# fpga-serdes-power.net
KiCad netlist of a schematic drawn in Altium Designer
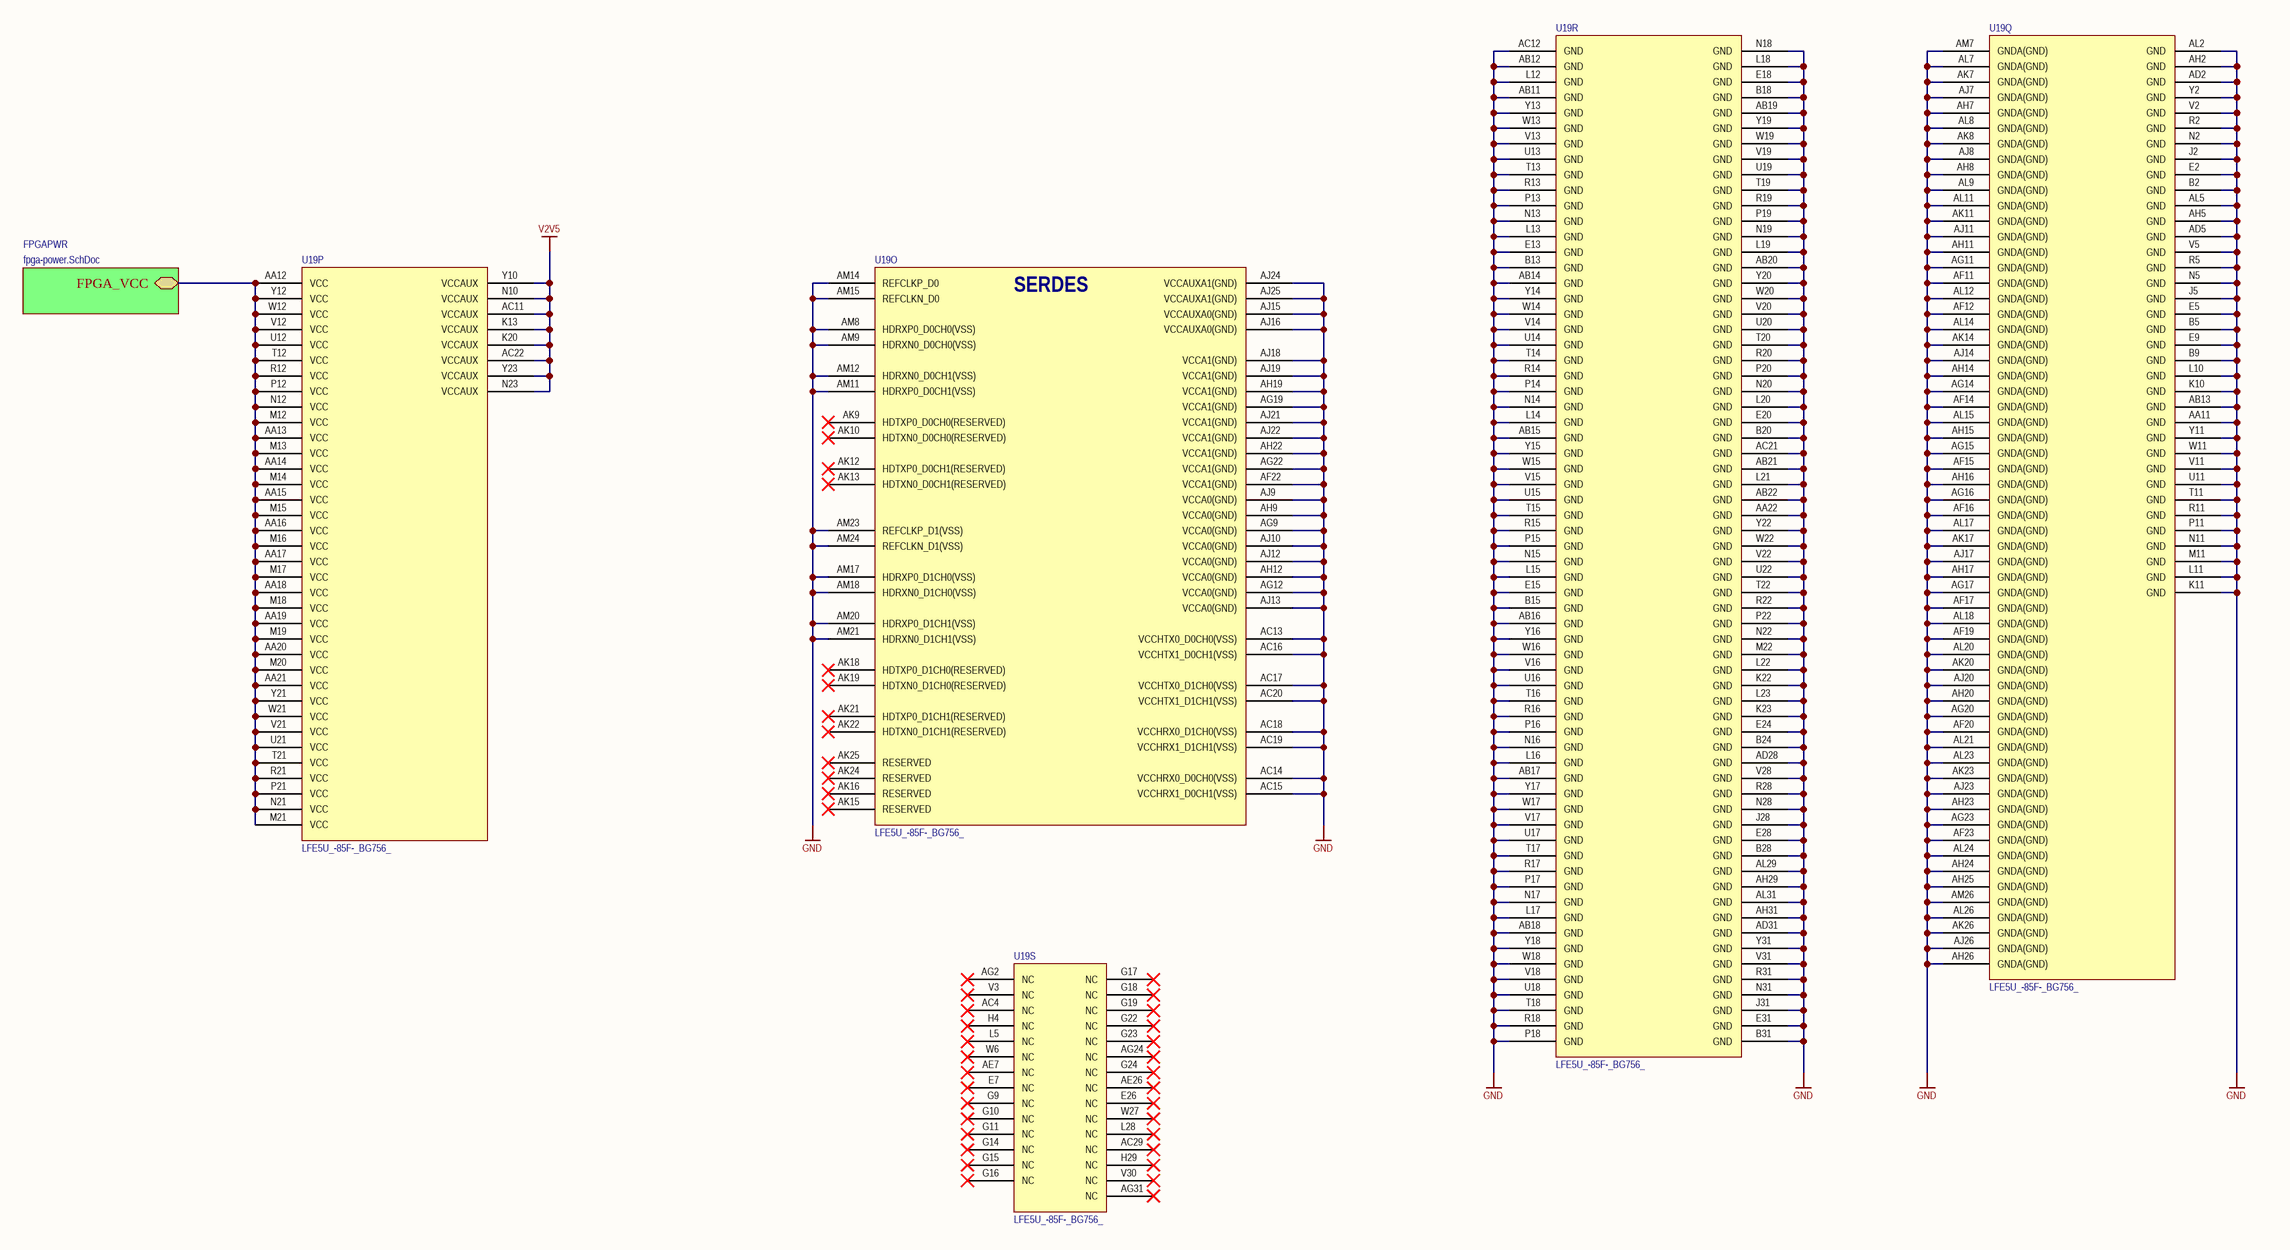
[diagram p0: fpga-serdes-power.SchDoc]

(export (version "E")
  (design (tool "Eeschema 10.0.6"))
  (components
    (comp (ref "U19")
      (value "LFE5U_-85F-_BG756_")
      (footprint "lattice:caBGA756")
      (description "ECP5 FPGA, 85k LUT, 756-caBGA")
      (fields (field (name "MANUFACTURER") "Lattice Semiconductor"))
      (libsource (lib "lattice") (part "LFE5U_-85F-_BG756_"))
    )
  )
  (nets
    (net (code "1") (name "/FPGA_VCC") (class "Default")
      (node (ref "U19") (pin "AA12") (pinfunction "VCC_AA12") (pintype "power_in"))
      (node (ref "U19") (pin "AA13") (pinfunction "VCC_AA13") (pintype "power_in"))
      (node (ref "U19") (pin "AA14") (pinfunction "VCC_AA14") (pintype "power_in"))
      (node (ref "U19") (pin "AA15") (pinfunction "VCC_AA15") (pintype "power_in"))
      (node (ref "U19") (pin "AA16") (pinfunction "VCC_AA16") (pintype "power_in"))
      (node (ref "U19") (pin "AA17") (pinfunction "VCC_AA17") (pintype "power_in"))
      (node (ref "U19") (pin "AA18") (pinfunction "VCC_AA18") (pintype "power_in"))
      (node (ref "U19") (pin "AA19") (pinfunction "VCC_AA19") (pintype "power_in"))
      (node (ref "U19") (pin "AA20") (pinfunction "VCC_AA20") (pintype "power_in"))
      (node (ref "U19") (pin "AA21") (pinfunction "VCC_AA21") (pintype "power_in"))
      (node (ref "U19") (pin "M12") (pinfunction "VCC_M12") (pintype "power_in"))
      (node (ref "U19") (pin "M13") (pinfunction "VCC_M13") (pintype "power_in"))
      (node (ref "U19") (pin "M14") (pinfunction "VCC_M14") (pintype "power_in"))
      (node (ref "U19") (pin "M15") (pinfunction "VCC_M15") (pintype "power_in"))
      (node (ref "U19") (pin "M16") (pinfunction "VCC_M16") (pintype "power_in"))
      (node (ref "U19") (pin "M17") (pinfunction "VCC_M17") (pintype "power_in"))
      (node (ref "U19") (pin "M18") (pinfunction "VCC_M18") (pintype "power_in"))
      (node (ref "U19") (pin "M19") (pinfunction "VCC_M19") (pintype "power_in"))
      (node (ref "U19") (pin "M20") (pinfunction "VCC_M20") (pintype "power_in"))
      (node (ref "U19") (pin "M21") (pinfunction "VCC_M21") (pintype "power_in"))
      (node (ref "U19") (pin "N12") (pinfunction "VCC_N12") (pintype "power_in"))
      (node (ref "U19") (pin "N21") (pinfunction "VCC_N21") (pintype "power_in"))
      (node (ref "U19") (pin "P12") (pinfunction "VCC_P12") (pintype "power_in"))
      (node (ref "U19") (pin "P21") (pinfunction "VCC_P21") (pintype "power_in"))
      (node (ref "U19") (pin "R12") (pinfunction "VCC_R12") (pintype "power_in"))
      (node (ref "U19") (pin "R21") (pinfunction "VCC_R21") (pintype "power_in"))
      (node (ref "U19") (pin "T12") (pinfunction "VCC_T12") (pintype "power_in"))
      (node (ref "U19") (pin "T21") (pinfunction "VCC_T21") (pintype "power_in"))
      (node (ref "U19") (pin "U12") (pinfunction "VCC_U12") (pintype "power_in"))
      (node (ref "U19") (pin "U21") (pinfunction "VCC_U21") (pintype "power_in"))
      (node (ref "U19") (pin "V12") (pinfunction "VCC_V12") (pintype "power_in"))
      (node (ref "U19") (pin "V21") (pinfunction "VCC_V21") (pintype "power_in"))
      (node (ref "U19") (pin "W12") (pinfunction "VCC_W12") (pintype "power_in"))
      (node (ref "U19") (pin "W21") (pinfunction "VCC_W21") (pintype "power_in"))
      (node (ref "U19") (pin "Y12") (pinfunction "VCC_Y12") (pintype "power_in"))
      (node (ref "U19") (pin "Y21") (pinfunction "VCC_Y21") (pintype "power_in"))
    )
    (net (code "2") (name "GND") (class "Default")
      (node (ref "U19") (pin "AA11") (pinfunction "GND_AA11") (pintype "power_in"))
      (node (ref "U19") (pin "AA22") (pinfunction "GND_AA22") (pintype "power_in"))
      (node (ref "U19") (pin "AB11") (pinfunction "GND_AB11") (pintype "power_in"))
      (node (ref "U19") (pin "AB12") (pinfunction "GND_AB12") (pintype "power_in"))
      (node (ref "U19") (pin "AB13") (pinfunction "GND_AB13") (pintype "power_in"))
      (node (ref "U19") (pin "AB14") (pinfunction "GND_AB14") (pintype "power_in"))
      (node (ref "U19") (pin "AB15") (pinfunction "GND_AB15") (pintype "power_in"))
      (node (ref "U19") (pin "AB16") (pinfunction "GND_AB16") (pintype "power_in"))
      (node (ref "U19") (pin "AB17") (pinfunction "GND_AB17") (pintype "power_in"))
      (node (ref "U19") (pin "AB18") (pinfunction "GND_AB18") (pintype "power_in"))
      (node (ref "U19") (pin "AB19") (pinfunction "GND_AB19") (pintype "power_in"))
      (node (ref "U19") (pin "AB20") (pinfunction "GND_AB20") (pintype "power_in"))
      (node (ref "U19") (pin "AB21") (pinfunction "GND_AB21") (pintype "power_in"))
      (node (ref "U19") (pin "AB22") (pinfunction "GND_AB22") (pintype "power_in"))
      (node (ref "U19") (pin "AC12") (pinfunction "GND_AC12") (pintype "power_in"))
      (node (ref "U19") (pin "AC13") (pinfunction "VCCHTX0_D0CH0(VSS)_AC13") (pintype "power_in"))
      (node (ref "U19") (pin "AC14") (pinfunction "VCCHRX0_D0CH0(VSS)_AC14") (pintype "power_in"))
      (node (ref "U19") (pin "AC15") (pinfunction "VCCHRX1_D0CH1(VSS)_AC15") (pintype "power_in"))
      (node (ref "U19") (pin "AC16") (pinfunction "VCCHTX1_D0CH1(VSS)_AC16") (pintype "power_in"))
      (node (ref "U19") (pin "AC17") (pinfunction "VCCHTX0_D1CH0(VSS)_AC17") (pintype "power_in"))
      (node (ref "U19") (pin "AC18") (pinfunction "VCCHRX0_D1CH0(VSS)_AC18") (pintype "power_in"))
      (node (ref "U19") (pin "AC19") (pinfunction "VCCHRX1_D1CH1(VSS)_AC19") (pintype "power_in"))
      (node (ref "U19") (pin "AC20") (pinfunction "VCCHTX1_D1CH1(VSS)_AC20") (pintype "power_in"))
      (node (ref "U19") (pin "AC21") (pinfunction "GND_AC21") (pintype "power_in"))
      (node (ref "U19") (pin "AD2") (pinfunction "GND_AD2") (pintype "power_in"))
      (node (ref "U19") (pin "AD28") (pinfunction "GND_AD28") (pintype "power_in"))
      (node (ref "U19") (pin "AD31") (pinfunction "GND_AD31") (pintype "power_in"))
      (node (ref "U19") (pin "AD5") (pinfunction "GND_AD5") (pintype "power_in"))
      (node (ref "U19") (pin "AF11") (pinfunction "GNDA(GND)_AF11") (pintype "power_in"))
      (node (ref "U19") (pin "AF12") (pinfunction "GNDA(GND)_AF12") (pintype "power_in"))
      (node (ref "U19") (pin "AF14") (pinfunction "GNDA(GND)_AF14") (pintype "power_in"))
      (node (ref "U19") (pin "AF15") (pinfunction "GNDA(GND)_AF15") (pintype "power_in"))
      (node (ref "U19") (pin "AF16") (pinfunction "GNDA(GND)_AF16") (pintype "power_in"))
      (node (ref "U19") (pin "AF17") (pinfunction "GNDA(GND)_AF17") (pintype "power_in"))
      (node (ref "U19") (pin "AF19") (pinfunction "GNDA(GND)_AF19") (pintype "power_in"))
      (node (ref "U19") (pin "AF20") (pinfunction "GNDA(GND)_AF20") (pintype "power_in"))
      (node (ref "U19") (pin "AF22") (pinfunction "VCCA1(GND)_AF22") (pintype "power_in"))
      (node (ref "U19") (pin "AF23") (pinfunction "GNDA(GND)_AF23") (pintype "power_in"))
      (node (ref "U19") (pin "AG11") (pinfunction "GNDA(GND)_AG11") (pintype "power_in"))
      (node (ref "U19") (pin "AG12") (pinfunction "VCCA0(GND)_AG12") (pintype "power_in"))
      (node (ref "U19") (pin "AG14") (pinfunction "GNDA(GND)_AG14") (pintype "power_in"))
      (node (ref "U19") (pin "AG15") (pinfunction "GNDA(GND)_AG15") (pintype "power_in"))
      (node (ref "U19") (pin "AG16") (pinfunction "GNDA(GND)_AG16") (pintype "power_in"))
      (node (ref "U19") (pin "AG17") (pinfunction "GNDA(GND)_AG17") (pintype "power_in"))
      (node (ref "U19") (pin "AG19") (pinfunction "VCCA1(GND)_AG19") (pintype "power_in"))
      (node (ref "U19") (pin "AG20") (pinfunction "GNDA(GND)_AG20") (pintype "power_in"))
      (node (ref "U19") (pin "AG22") (pinfunction "VCCA1(GND)_AG22") (pintype "power_in"))
      (node (ref "U19") (pin "AG23") (pinfunction "GNDA(GND)_AG23") (pintype "power_in"))
      (node (ref "U19") (pin "AG9") (pinfunction "VCCA0(GND)_AG9") (pintype "power_in"))
      (node (ref "U19") (pin "AH11") (pinfunction "GNDA(GND)_AH11") (pintype "power_in"))
      (node (ref "U19") (pin "AH12") (pinfunction "VCCA0(GND)_AH12") (pintype "power_in"))
      (node (ref "U19") (pin "AH14") (pinfunction "GNDA(GND)_AH14") (pintype "power_in"))
      (node (ref "U19") (pin "AH15") (pinfunction "GNDA(GND)_AH15") (pintype "power_in"))
      (node (ref "U19") (pin "AH16") (pinfunction "GNDA(GND)_AH16") (pintype "power_in"))
      (node (ref "U19") (pin "AH17") (pinfunction "GNDA(GND)_AH17") (pintype "power_in"))
      (node (ref "U19") (pin "AH19") (pinfunction "VCCA1(GND)_AH19") (pintype "power_in"))
      (node (ref "U19") (pin "AH2") (pinfunction "GND_AH2") (pintype "power_in"))
      (node (ref "U19") (pin "AH20") (pinfunction "GNDA(GND)_AH20") (pintype "power_in"))
      (node (ref "U19") (pin "AH22") (pinfunction "VCCA1(GND)_AH22") (pintype "power_in"))
      (node (ref "U19") (pin "AH23") (pinfunction "GNDA(GND)_AH23") (pintype "power_in"))
      (node (ref "U19") (pin "AH24") (pinfunction "GNDA(GND)_AH24") (pintype "power_in"))
      (node (ref "U19") (pin "AH25") (pinfunction "GNDA(GND)_AH25") (pintype "power_in"))
      (node (ref "U19") (pin "AH26") (pinfunction "GNDA(GND)_AH26") (pintype "power_in"))
      (node (ref "U19") (pin "AH29") (pinfunction "GND_AH29") (pintype "power_in"))
      (node (ref "U19") (pin "AH31") (pinfunction "GND_AH31") (pintype "power_in"))
      (node (ref "U19") (pin "AH5") (pinfunction "GND_AH5") (pintype "power_in"))
      (node (ref "U19") (pin "AH7") (pinfunction "GNDA(GND)_AH7") (pintype "power_in"))
      (node (ref "U19") (pin "AH8") (pinfunction "GNDA(GND)_AH8") (pintype "power_in"))
      (node (ref "U19") (pin "AH9") (pinfunction "VCCA0(GND)_AH9") (pintype "power_in"))
      (node (ref "U19") (pin "AJ10") (pinfunction "VCCA0(GND)_AJ10") (pintype "power_in"))
      (node (ref "U19") (pin "AJ11") (pinfunction "GNDA(GND)_AJ11") (pintype "power_in"))
      (node (ref "U19") (pin "AJ12") (pinfunction "VCCA0(GND)_AJ12") (pintype "power_in"))
      (node (ref "U19") (pin "AJ13") (pinfunction "VCCA0(GND)_AJ13") (pintype "power_in"))
      (node (ref "U19") (pin "AJ14") (pinfunction "GNDA(GND)_AJ14") (pintype "power_in"))
      (node (ref "U19") (pin "AJ15") (pinfunction "VCCAUXA0(GND)_AJ15") (pintype "power_in"))
      (node (ref "U19") (pin "AJ16") (pinfunction "VCCAUXA0(GND)_AJ16") (pintype "power_in"))
      (node (ref "U19") (pin "AJ17") (pinfunction "GNDA(GND)_AJ17") (pintype "power_in"))
      (node (ref "U19") (pin "AJ18") (pinfunction "VCCA1(GND)_AJ18") (pintype "power_in"))
      (node (ref "U19") (pin "AJ19") (pinfunction "VCCA1(GND)_AJ19") (pintype "power_in"))
      (node (ref "U19") (pin "AJ20") (pinfunction "GNDA(GND)_AJ20") (pintype "power_in"))
      (node (ref "U19") (pin "AJ21") (pinfunction "VCCA1(GND)_AJ21") (pintype "power_in"))
      (node (ref "U19") (pin "AJ22") (pinfunction "VCCA1(GND)_AJ22") (pintype "power_in"))
      (node (ref "U19") (pin "AJ23") (pinfunction "GNDA(GND)_AJ23") (pintype "power_in"))
      (node (ref "U19") (pin "AJ24") (pinfunction "VCCAUXA1(GND)_AJ24") (pintype "power_in"))
      (node (ref "U19") (pin "AJ25") (pinfunction "VCCAUXA1(GND)_AJ25") (pintype "power_in"))
      (node (ref "U19") (pin "AJ26") (pinfunction "GNDA(GND)_AJ26") (pintype "power_in"))
      (node (ref "U19") (pin "AJ7") (pinfunction "GNDA(GND)_AJ7") (pintype "power_in"))
      (node (ref "U19") (pin "AJ8") (pinfunction "GNDA(GND)_AJ8") (pintype "power_in"))
      (node (ref "U19") (pin "AJ9") (pinfunction "VCCA0(GND)_AJ9") (pintype "power_in"))
      (node (ref "U19") (pin "AK11") (pinfunction "GNDA(GND)_AK11") (pintype "power_in"))
      (node (ref "U19") (pin "AK14") (pinfunction "GNDA(GND)_AK14") (pintype "power_in"))
      (node (ref "U19") (pin "AK17") (pinfunction "GNDA(GND)_AK17") (pintype "power_in"))
      (node (ref "U19") (pin "AK20") (pinfunction "GNDA(GND)_AK20") (pintype "power_in"))
      (node (ref "U19") (pin "AK23") (pinfunction "GNDA(GND)_AK23") (pintype "power_in"))
      (node (ref "U19") (pin "AK26") (pinfunction "GNDA(GND)_AK26") (pintype "power_in"))
      (node (ref "U19") (pin "AK7") (pinfunction "GNDA(GND)_AK7") (pintype "power_in"))
      (node (ref "U19") (pin "AK8") (pinfunction "GNDA(GND)_AK8") (pintype "power_in"))
      (node (ref "U19") (pin "AL11") (pinfunction "GNDA(GND)_AL11") (pintype "power_in"))
      (node (ref "U19") (pin "AL12") (pinfunction "GNDA(GND)_AL12") (pintype "power_in"))
      (node (ref "U19") (pin "AL14") (pinfunction "GNDA(GND)_AL14") (pintype "power_in"))
      (node (ref "U19") (pin "AL15") (pinfunction "GNDA(GND)_AL15") (pintype "power_in"))
      (node (ref "U19") (pin "AL17") (pinfunction "GNDA(GND)_AL17") (pintype "power_in"))
      (node (ref "U19") (pin "AL18") (pinfunction "GNDA(GND)_AL18") (pintype "power_in"))
      (node (ref "U19") (pin "AL2") (pinfunction "GND_AL2") (pintype "power_in"))
      (node (ref "U19") (pin "AL20") (pinfunction "GNDA(GND)_AL20") (pintype "power_in"))
      (node (ref "U19") (pin "AL21") (pinfunction "GNDA(GND)_AL21") (pintype "power_in"))
      (node (ref "U19") (pin "AL23") (pinfunction "GNDA(GND)_AL23") (pintype "power_in"))
      (node (ref "U19") (pin "AL24") (pinfunction "GNDA(GND)_AL24") (pintype "power_in"))
      (node (ref "U19") (pin "AL26") (pinfunction "GNDA(GND)_AL26") (pintype "power_in"))
      (node (ref "U19") (pin "AL29") (pinfunction "GND_AL29") (pintype "power_in"))
      (node (ref "U19") (pin "AL31") (pinfunction "GND_AL31") (pintype "power_in"))
      (node (ref "U19") (pin "AL5") (pinfunction "GND_AL5") (pintype "power_in"))
      (node (ref "U19") (pin "AL7") (pinfunction "GNDA(GND)_AL7") (pintype "power_in"))
      (node (ref "U19") (pin "AL8") (pinfunction "GNDA(GND)_AL8") (pintype "power_in"))
      (node (ref "U19") (pin "AL9") (pinfunction "GNDA(GND)_AL9") (pintype "power_in"))
      (node (ref "U19") (pin "AM11") (pinfunction "HDRXP0_D0CH1(VSS)_AM11") (pintype "passive"))
      (node (ref "U19") (pin "AM12") (pinfunction "HDRXN0_D0CH1(VSS)_AM12") (pintype "passive"))
      (node (ref "U19") (pin "AM14") (pinfunction "REFCLKP_D0_AM14") (pintype "passive"))
      (node (ref "U19") (pin "AM15") (pinfunction "REFCLKN_D0_AM15") (pintype "passive"))
      (node (ref "U19") (pin "AM17") (pinfunction "HDRXP0_D1CH0(VSS)_AM17") (pintype "passive"))
      (node (ref "U19") (pin "AM18") (pinfunction "HDRXN0_D1CH0(VSS)_AM18") (pintype "passive"))
      (node (ref "U19") (pin "AM20") (pinfunction "HDRXP0_D1CH1(VSS)_AM20") (pintype "passive"))
      (node (ref "U19") (pin "AM21") (pinfunction "HDRXN0_D1CH1(VSS)_AM21") (pintype "passive"))
      (node (ref "U19") (pin "AM23") (pinfunction "REFCLKP_D1(VSS)_AM23") (pintype "passive"))
      (node (ref "U19") (pin "AM24") (pinfunction "REFCLKN_D1(VSS)_AM24") (pintype "passive"))
      (node (ref "U19") (pin "AM26") (pinfunction "GNDA(GND)_AM26") (pintype "power_in"))
      (node (ref "U19") (pin "AM7") (pinfunction "GNDA(GND)_AM7") (pintype "power_in"))
      (node (ref "U19") (pin "AM8") (pinfunction "HDRXP0_D0CH0(VSS)_AM8") (pintype "passive"))
      (node (ref "U19") (pin "AM9") (pinfunction "HDRXN0_D0CH0(VSS)_AM9") (pintype "passive"))
      (node (ref "U19") (pin "B13") (pinfunction "GND_B13") (pintype "power_in"))
      (node (ref "U19") (pin "B15") (pinfunction "GND_B15") (pintype "power_in"))
      (node (ref "U19") (pin "B18") (pinfunction "GND_B18") (pintype "power_in"))
      (node (ref "U19") (pin "B2") (pinfunction "GND_B2") (pintype "power_in"))
      (node (ref "U19") (pin "B20") (pinfunction "GND_B20") (pintype "power_in"))
      (node (ref "U19") (pin "B24") (pinfunction "GND_B24") (pintype "power_in"))
      (node (ref "U19") (pin "B28") (pinfunction "GND_B28") (pintype "power_in"))
      (node (ref "U19") (pin "B31") (pinfunction "GND_B31") (pintype "power_in"))
      (node (ref "U19") (pin "B5") (pinfunction "GND_B5") (pintype "power_in"))
      (node (ref "U19") (pin "B9") (pinfunction "GND_B9") (pintype "power_in"))
      (node (ref "U19") (pin "E13") (pinfunction "GND_E13") (pintype "power_in"))
      (node (ref "U19") (pin "E15") (pinfunction "GND_E15") (pintype "power_in"))
      (node (ref "U19") (pin "E18") (pinfunction "GND_E18") (pintype "power_in"))
      (node (ref "U19") (pin "E2") (pinfunction "GND_E2") (pintype "power_in"))
      (node (ref "U19") (pin "E20") (pinfunction "GND_E20") (pintype "power_in"))
      (node (ref "U19") (pin "E24") (pinfunction "GND_E24") (pintype "power_in"))
      (node (ref "U19") (pin "E28") (pinfunction "GND_E28") (pintype "power_in"))
      (node (ref "U19") (pin "E31") (pinfunction "GND_E31") (pintype "power_in"))
      (node (ref "U19") (pin "E5") (pinfunction "GND_E5") (pintype "power_in"))
      (node (ref "U19") (pin "E9") (pinfunction "GND_E9") (pintype "power_in"))
      (node (ref "U19") (pin "J2") (pinfunction "GND_J2") (pintype "power_in"))
      (node (ref "U19") (pin "J28") (pinfunction "GND_J28") (pintype "power_in"))
      (node (ref "U19") (pin "J31") (pinfunction "GND_J31") (pintype "power_in"))
      (node (ref "U19") (pin "J5") (pinfunction "GND_J5") (pintype "power_in"))
      (node (ref "U19") (pin "K10") (pinfunction "GND_K10") (pintype "power_in"))
      (node (ref "U19") (pin "K11") (pinfunction "GND_K11") (pintype "power_in"))
      (node (ref "U19") (pin "K22") (pinfunction "GND_K22") (pintype "power_in"))
      (node (ref "U19") (pin "K23") (pinfunction "GND_K23") (pintype "power_in"))
      (node (ref "U19") (pin "L10") (pinfunction "GND_L10") (pintype "power_in"))
      (node (ref "U19") (pin "L11") (pinfunction "GND_L11") (pintype "power_in"))
      (node (ref "U19") (pin "L12") (pinfunction "GND_L12") (pintype "power_in"))
      (node (ref "U19") (pin "L13") (pinfunction "GND_L13") (pintype "power_in"))
      (node (ref "U19") (pin "L14") (pinfunction "GND_L14") (pintype "power_in"))
      (node (ref "U19") (pin "L15") (pinfunction "GND_L15") (pintype "power_in"))
      (node (ref "U19") (pin "L16") (pinfunction "GND_L16") (pintype "power_in"))
      (node (ref "U19") (pin "L17") (pinfunction "GND_L17") (pintype "power_in"))
      (node (ref "U19") (pin "L18") (pinfunction "GND_L18") (pintype "power_in"))
      (node (ref "U19") (pin "L19") (pinfunction "GND_L19") (pintype "power_in"))
      (node (ref "U19") (pin "L20") (pinfunction "GND_L20") (pintype "power_in"))
      (node (ref "U19") (pin "L21") (pinfunction "GND_L21") (pintype "power_in"))
      (node (ref "U19") (pin "L22") (pinfunction "GND_L22") (pintype "power_in"))
      (node (ref "U19") (pin "L23") (pinfunction "GND_L23") (pintype "power_in"))
      (node (ref "U19") (pin "M11") (pinfunction "GND_M11") (pintype "power_in"))
      (node (ref "U19") (pin "M22") (pinfunction "GND_M22") (pintype "power_in"))
      (node (ref "U19") (pin "N11") (pinfunction "GND_N11") (pintype "power_in"))
      (node (ref "U19") (pin "N13") (pinfunction "GND_N13") (pintype "power_in"))
      (node (ref "U19") (pin "N14") (pinfunction "GND_N14") (pintype "power_in"))
      (node (ref "U19") (pin "N15") (pinfunction "GND_N15") (pintype "power_in"))
      (node (ref "U19") (pin "N16") (pinfunction "GND_N16") (pintype "power_in"))
      (node (ref "U19") (pin "N17") (pinfunction "GND_N17") (pintype "power_in"))
      (node (ref "U19") (pin "N18") (pinfunction "GND_N18") (pintype "power_in"))
      (node (ref "U19") (pin "N19") (pinfunction "GND_N19") (pintype "power_in"))
      (node (ref "U19") (pin "N2") (pinfunction "GND_N2") (pintype "power_in"))
      (node (ref "U19") (pin "N20") (pinfunction "GND_N20") (pintype "power_in"))
      (node (ref "U19") (pin "N22") (pinfunction "GND_N22") (pintype "power_in"))
      (node (ref "U19") (pin "N28") (pinfunction "GND_N28") (pintype "power_in"))
      (node (ref "U19") (pin "N31") (pinfunction "GND_N31") (pintype "power_in"))
      (node (ref "U19") (pin "N5") (pinfunction "GND_N5") (pintype "power_in"))
      (node (ref "U19") (pin "P11") (pinfunction "GND_P11") (pintype "power_in"))
      (node (ref "U19") (pin "P13") (pinfunction "GND_P13") (pintype "power_in"))
      (node (ref "U19") (pin "P14") (pinfunction "GND_P14") (pintype "power_in"))
      (node (ref "U19") (pin "P15") (pinfunction "GND_P15") (pintype "power_in"))
      (node (ref "U19") (pin "P16") (pinfunction "GND_P16") (pintype "power_in"))
      (node (ref "U19") (pin "P17") (pinfunction "GND_P17") (pintype "power_in"))
      (node (ref "U19") (pin "P18") (pinfunction "GND_P18") (pintype "power_in"))
      (node (ref "U19") (pin "P19") (pinfunction "GND_P19") (pintype "power_in"))
      (node (ref "U19") (pin "P20") (pinfunction "GND_P20") (pintype "power_in"))
      (node (ref "U19") (pin "P22") (pinfunction "GND_P22") (pintype "power_in"))
      (node (ref "U19") (pin "R11") (pinfunction "GND_R11") (pintype "power_in"))
      (node (ref "U19") (pin "R13") (pinfunction "GND_R13") (pintype "power_in"))
      (node (ref "U19") (pin "R14") (pinfunction "GND_R14") (pintype "power_in"))
      (node (ref "U19") (pin "R15") (pinfunction "GND_R15") (pintype "power_in"))
      (node (ref "U19") (pin "R16") (pinfunction "GND_R16") (pintype "power_in"))
      (node (ref "U19") (pin "R17") (pinfunction "GND_R17") (pintype "power_in"))
      (node (ref "U19") (pin "R18") (pinfunction "GND_R18") (pintype "power_in"))
      (node (ref "U19") (pin "R19") (pinfunction "GND_R19") (pintype "power_in"))
      (node (ref "U19") (pin "R2") (pinfunction "GND_R2") (pintype "power_in"))
      (node (ref "U19") (pin "R20") (pinfunction "GND_R20") (pintype "power_in"))
      (node (ref "U19") (pin "R22") (pinfunction "GND_R22") (pintype "power_in"))
      (node (ref "U19") (pin "R28") (pinfunction "GND_R28") (pintype "power_in"))
      (node (ref "U19") (pin "R31") (pinfunction "GND_R31") (pintype "power_in"))
      (node (ref "U19") (pin "R5") (pinfunction "GND_R5") (pintype "power_in"))
      (node (ref "U19") (pin "T11") (pinfunction "GND_T11") (pintype "power_in"))
      (node (ref "U19") (pin "T13") (pinfunction "GND_T13") (pintype "power_in"))
      (node (ref "U19") (pin "T14") (pinfunction "GND_T14") (pintype "power_in"))
      (node (ref "U19") (pin "T15") (pinfunction "GND_T15") (pintype "power_in"))
      (node (ref "U19") (pin "T16") (pinfunction "GND_T16") (pintype "power_in"))
      (node (ref "U19") (pin "T17") (pinfunction "GND_T17") (pintype "power_in"))
      (node (ref "U19") (pin "T18") (pinfunction "GND_T18") (pintype "power_in"))
      (node (ref "U19") (pin "T19") (pinfunction "GND_T19") (pintype "power_in"))
      (node (ref "U19") (pin "T20") (pinfunction "GND_T20") (pintype "power_in"))
      (node (ref "U19") (pin "T22") (pinfunction "GND_T22") (pintype "power_in"))
      (node (ref "U19") (pin "U11") (pinfunction "GND_U11") (pintype "power_in"))
      (node (ref "U19") (pin "U13") (pinfunction "GND_U13") (pintype "power_in"))
      (node (ref "U19") (pin "U14") (pinfunction "GND_U14") (pintype "power_in"))
      (node (ref "U19") (pin "U15") (pinfunction "GND_U15") (pintype "power_in"))
      (node (ref "U19") (pin "U16") (pinfunction "GND_U16") (pintype "power_in"))
      (node (ref "U19") (pin "U17") (pinfunction "GND_U17") (pintype "power_in"))
      (node (ref "U19") (pin "U18") (pinfunction "GND_U18") (pintype "power_in"))
      (node (ref "U19") (pin "U19") (pinfunction "GND_U19") (pintype "power_in"))
      (node (ref "U19") (pin "U20") (pinfunction "GND_U20") (pintype "power_in"))
      (node (ref "U19") (pin "U22") (pinfunction "GND_U22") (pintype "power_in"))
      (node (ref "U19") (pin "V11") (pinfunction "GND_V11") (pintype "power_in"))
      (node (ref "U19") (pin "V13") (pinfunction "GND_V13") (pintype "power_in"))
      (node (ref "U19") (pin "V14") (pinfunction "GND_V14") (pintype "power_in"))
      (node (ref "U19") (pin "V15") (pinfunction "GND_V15") (pintype "power_in"))
      (node (ref "U19") (pin "V16") (pinfunction "GND_V16") (pintype "power_in"))
      (node (ref "U19") (pin "V17") (pinfunction "GND_V17") (pintype "power_in"))
      (node (ref "U19") (pin "V18") (pinfunction "GND_V18") (pintype "power_in"))
      (node (ref "U19") (pin "V19") (pinfunction "GND_V19") (pintype "power_in"))
      (node (ref "U19") (pin "V2") (pinfunction "GND_V2") (pintype "power_in"))
      (node (ref "U19") (pin "V20") (pinfunction "GND_V20") (pintype "power_in"))
      (node (ref "U19") (pin "V22") (pinfunction "GND_V22") (pintype "power_in"))
      (node (ref "U19") (pin "V28") (pinfunction "GND_V28") (pintype "power_in"))
      (node (ref "U19") (pin "V31") (pinfunction "GND_V31") (pintype "power_in"))
      (node (ref "U19") (pin "V5") (pinfunction "GND_V5") (pintype "power_in"))
      (node (ref "U19") (pin "W11") (pinfunction "GND_W11") (pintype "power_in"))
      (node (ref "U19") (pin "W13") (pinfunction "GND_W13") (pintype "power_in"))
      (node (ref "U19") (pin "W14") (pinfunction "GND_W14") (pintype "power_in"))
      (node (ref "U19") (pin "W15") (pinfunction "GND_W15") (pintype "power_in"))
      (node (ref "U19") (pin "W16") (pinfunction "GND_W16") (pintype "power_in"))
      (node (ref "U19") (pin "W17") (pinfunction "GND_W17") (pintype "power_in"))
      (node (ref "U19") (pin "W18") (pinfunction "GND_W18") (pintype "power_in"))
      (node (ref "U19") (pin "W19") (pinfunction "GND_W19") (pintype "power_in"))
      (node (ref "U19") (pin "W20") (pinfunction "GND_W20") (pintype "power_in"))
      (node (ref "U19") (pin "W22") (pinfunction "GND_W22") (pintype "power_in"))
      (node (ref "U19") (pin "Y11") (pinfunction "GND_Y11") (pintype "power_in"))
      (node (ref "U19") (pin "Y13") (pinfunction "GND_Y13") (pintype "power_in"))
      (node (ref "U19") (pin "Y14") (pinfunction "GND_Y14") (pintype "power_in"))
      (node (ref "U19") (pin "Y15") (pinfunction "GND_Y15") (pintype "power_in"))
      (node (ref "U19") (pin "Y16") (pinfunction "GND_Y16") (pintype "power_in"))
      (node (ref "U19") (pin "Y17") (pinfunction "GND_Y17") (pintype "power_in"))
      (node (ref "U19") (pin "Y18") (pinfunction "GND_Y18") (pintype "power_in"))
      (node (ref "U19") (pin "Y19") (pinfunction "GND_Y19") (pintype "power_in"))
      (node (ref "U19") (pin "Y2") (pinfunction "GND_Y2") (pintype "power_in"))
      (node (ref "U19") (pin "Y20") (pinfunction "GND_Y20") (pintype "power_in"))
      (node (ref "U19") (pin "Y22") (pinfunction "GND_Y22") (pintype "power_in"))
      (node (ref "U19") (pin "Y31") (pinfunction "GND_Y31") (pintype "power_in"))
    )
    (net (code "3") (name "V2V5") (class "Default")
      (node (ref "U19") (pin "AC11") (pinfunction "VCCAUX_AC11") (pintype "power_in"))
      (node (ref "U19") (pin "AC22") (pinfunction "VCCAUX_AC22") (pintype "power_in"))
      (node (ref "U19") (pin "K13") (pinfunction "VCCAUX_K13") (pintype "power_in"))
      (node (ref "U19") (pin "K20") (pinfunction "VCCAUX_K20") (pintype "power_in"))
      (node (ref "U19") (pin "N10") (pinfunction "VCCAUX_N10") (pintype "power_in"))
      (node (ref "U19") (pin "N23") (pinfunction "VCCAUX_N23") (pintype "power_in"))
      (node (ref "U19") (pin "Y10") (pinfunction "VCCAUX_Y10") (pintype "power_in"))
      (node (ref "U19") (pin "Y23") (pinfunction "VCCAUX_Y23") (pintype "power_in"))
    )
    (net (code "4") (name "unconnected-(U19O-HDTXN0_D0CH0(RESERVED)-PadAK10)") (class "Default")
      (node (ref "U19") (pin "AK10") (pinfunction "HDTXN0_D0CH0(RESERVED)_AK10") (pintype "passive+no_connect"))
    )
    (net (code "5") (name "unconnected-(U19O-HDTXN0_D0CH1(RESERVED)-PadAK13)") (class "Default")
      (node (ref "U19") (pin "AK13") (pinfunction "HDTXN0_D0CH1(RESERVED)_AK13") (pintype "passive+no_connect"))
    )
    (net (code "6") (name "unconnected-(U19O-HDTXN0_D1CH0(RESERVED)-PadAK19)") (class "Default")
      (node (ref "U19") (pin "AK19") (pinfunction "HDTXN0_D1CH0(RESERVED)_AK19") (pintype "passive+no_connect"))
    )
    (net (code "7") (name "unconnected-(U19O-HDTXN0_D1CH1(RESERVED)-PadAK22)") (class "Default")
      (node (ref "U19") (pin "AK22") (pinfunction "HDTXN0_D1CH1(RESERVED)_AK22") (pintype "passive+no_connect"))
    )
    (net (code "8") (name "unconnected-(U19O-HDTXP0_D0CH0(RESERVED)-PadAK9)") (class "Default")
      (node (ref "U19") (pin "AK9") (pinfunction "HDTXP0_D0CH0(RESERVED)_AK9") (pintype "passive+no_connect"))
    )
    (net (code "9") (name "unconnected-(U19O-HDTXP0_D0CH1(RESERVED)-PadAK12)") (class "Default")
      (node (ref "U19") (pin "AK12") (pinfunction "HDTXP0_D0CH1(RESERVED)_AK12") (pintype "passive+no_connect"))
    )
    (net (code "10") (name "unconnected-(U19O-HDTXP0_D1CH0(RESERVED)-PadAK18)") (class "Default")
      (node (ref "U19") (pin "AK18") (pinfunction "HDTXP0_D1CH0(RESERVED)_AK18") (pintype "passive+no_connect"))
    )
    (net (code "11") (name "unconnected-(U19O-HDTXP0_D1CH1(RESERVED)-PadAK21)") (class "Default")
      (node (ref "U19") (pin "AK21") (pinfunction "HDTXP0_D1CH1(RESERVED)_AK21") (pintype "passive+no_connect"))
    )
    (net (code "12") (name "unconnected-(U19O-RESERVED-PadAK15)") (class "Default")
      (node (ref "U19") (pin "AK15") (pinfunction "RESERVED_AK15") (pintype "passive+no_connect"))
    )
    (net (code "13") (name "unconnected-(U19O-RESERVED-PadAK16)") (class "Default")
      (node (ref "U19") (pin "AK16") (pinfunction "RESERVED_AK16") (pintype "passive+no_connect"))
    )
    (net (code "14") (name "unconnected-(U19O-RESERVED-PadAK24)") (class "Default")
      (node (ref "U19") (pin "AK24") (pinfunction "RESERVED_AK24") (pintype "passive+no_connect"))
    )
    (net (code "15") (name "unconnected-(U19O-RESERVED-PadAK25)") (class "Default")
      (node (ref "U19") (pin "AK25") (pinfunction "RESERVED_AK25") (pintype "passive+no_connect"))
    )
    (net (code "16") (name "unconnected-(U19S-NC-PadAC4)") (class "Default")
      (node (ref "U19") (pin "AC4") (pinfunction "NC_AC4") (pintype "passive+no_connect"))
    )
    (net (code "17") (name "unconnected-(U19S-NC-PadAC29)") (class "Default")
      (node (ref "U19") (pin "AC29") (pinfunction "NC_AC29") (pintype "passive+no_connect"))
    )
    (net (code "18") (name "unconnected-(U19S-NC-PadAE7)") (class "Default")
      (node (ref "U19") (pin "AE7") (pinfunction "NC_AE7") (pintype "passive+no_connect"))
    )
    (net (code "19") (name "unconnected-(U19S-NC-PadAE26)") (class "Default")
      (node (ref "U19") (pin "AE26") (pinfunction "NC_AE26") (pintype "passive+no_connect"))
    )
    (net (code "20") (name "unconnected-(U19S-NC-PadAG2)") (class "Default")
      (node (ref "U19") (pin "AG2") (pinfunction "NC_AG2") (pintype "passive+no_connect"))
    )
    (net (code "21") (name "unconnected-(U19S-NC-PadAG24)") (class "Default")
      (node (ref "U19") (pin "AG24") (pinfunction "NC_AG24") (pintype "passive+no_connect"))
    )
    (net (code "22") (name "unconnected-(U19S-NC-PadAG31)") (class "Default")
      (node (ref "U19") (pin "AG31") (pinfunction "NC_AG31") (pintype "passive+no_connect"))
    )
    (net (code "23") (name "unconnected-(U19S-NC-PadE7)") (class "Default")
      (node (ref "U19") (pin "E7") (pinfunction "NC_E7") (pintype "passive+no_connect"))
    )
    (net (code "24") (name "unconnected-(U19S-NC-PadE26)") (class "Default")
      (node (ref "U19") (pin "E26") (pinfunction "NC_E26") (pintype "passive+no_connect"))
    )
    (net (code "25") (name "unconnected-(U19S-NC-PadG9)") (class "Default")
      (node (ref "U19") (pin "G9") (pinfunction "NC_G9") (pintype "passive+no_connect"))
    )
    (net (code "26") (name "unconnected-(U19S-NC-PadG10)") (class "Default")
      (node (ref "U19") (pin "G10") (pinfunction "NC_G10") (pintype "passive+no_connect"))
    )
    (net (code "27") (name "unconnected-(U19S-NC-PadG11)") (class "Default")
      (node (ref "U19") (pin "G11") (pinfunction "NC_G11") (pintype "passive+no_connect"))
    )
    (net (code "28") (name "unconnected-(U19S-NC-PadG14)") (class "Default")
      (node (ref "U19") (pin "G14") (pinfunction "NC_G14") (pintype "passive+no_connect"))
    )
    (net (code "29") (name "unconnected-(U19S-NC-PadG15)") (class "Default")
      (node (ref "U19") (pin "G15") (pinfunction "NC_G15") (pintype "passive+no_connect"))
    )
    (net (code "30") (name "unconnected-(U19S-NC-PadG16)") (class "Default")
      (node (ref "U19") (pin "G16") (pinfunction "NC_G16") (pintype "passive+no_connect"))
    )
    (net (code "31") (name "unconnected-(U19S-NC-PadG17)") (class "Default")
      (node (ref "U19") (pin "G17") (pinfunction "NC_G17") (pintype "passive+no_connect"))
    )
    (net (code "32") (name "unconnected-(U19S-NC-PadG18)") (class "Default")
      (node (ref "U19") (pin "G18") (pinfunction "NC_G18") (pintype "passive+no_connect"))
    )
    (net (code "33") (name "unconnected-(U19S-NC-PadG19)") (class "Default")
      (node (ref "U19") (pin "G19") (pinfunction "NC_G19") (pintype "passive+no_connect"))
    )
    (net (code "34") (name "unconnected-(U19S-NC-PadG22)") (class "Default")
      (node (ref "U19") (pin "G22") (pinfunction "NC_G22") (pintype "passive+no_connect"))
    )
    (net (code "35") (name "unconnected-(U19S-NC-PadG23)") (class "Default")
      (node (ref "U19") (pin "G23") (pinfunction "NC_G23") (pintype "passive+no_connect"))
    )
    (net (code "36") (name "unconnected-(U19S-NC-PadG24)") (class "Default")
      (node (ref "U19") (pin "G24") (pinfunction "NC_G24") (pintype "passive+no_connect"))
    )
    (net (code "37") (name "unconnected-(U19S-NC-PadH4)") (class "Default")
      (node (ref "U19") (pin "H4") (pinfunction "NC_H4") (pintype "passive+no_connect"))
    )
    (net (code "38") (name "unconnected-(U19S-NC-PadH29)") (class "Default")
      (node (ref "U19") (pin "H29") (pinfunction "NC_H29") (pintype "passive+no_connect"))
    )
    (net (code "39") (name "unconnected-(U19S-NC-PadL5)") (class "Default")
      (node (ref "U19") (pin "L5") (pinfunction "NC_L5") (pintype "passive+no_connect"))
    )
    (net (code "40") (name "unconnected-(U19S-NC-PadL28)") (class "Default")
      (node (ref "U19") (pin "L28") (pinfunction "NC_L28") (pintype "passive+no_connect"))
    )
    (net (code "41") (name "unconnected-(U19S-NC-PadV3)") (class "Default")
      (node (ref "U19") (pin "V3") (pinfunction "NC_V3") (pintype "passive+no_connect"))
    )
    (net (code "42") (name "unconnected-(U19S-NC-PadV30)") (class "Default")
      (node (ref "U19") (pin "V30") (pinfunction "NC_V30") (pintype "passive+no_connect"))
    )
    (net (code "43") (name "unconnected-(U19S-NC-PadW6)") (class "Default")
      (node (ref "U19") (pin "W6") (pinfunction "NC_W6") (pintype "passive+no_connect"))
    )
    (net (code "44") (name "unconnected-(U19S-NC-PadW27)") (class "Default")
      (node (ref "U19") (pin "W27") (pinfunction "NC_W27") (pintype "passive+no_connect"))
    )
  )
)
